# MAX4239_breakout.net
KiCad netlist of a schematic drawn in EAGLE
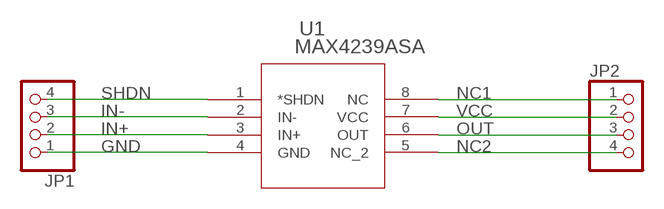
[diagram p0: schematic, sheet 1]

(export (version "E")
  (design (tool "Eeschema 10.0.6"))
  (components
    (comp (ref "JP1")
      (value "PINHD-1X4")
      (footprint "eagle-import:1X04")
      (libsource (lib "eagle-import") (part "PINHD-1X4"))
    )
    (comp (ref "JP2")
      (value "PINHD-1X4")
      (footprint "eagle-import:1X04")
      (libsource (lib "eagle-import") (part "PINHD-1X4"))
    )
    (comp (ref "U1")
      (value "MAX4239ASA")
      (footprint "eagle-import:21-0041B_8")
      (fields (field (name "MF") "Maxim Integrated") (field (name "MP") "MAX4239ASA+"))
      (libsource (lib "eagle-import") (part "MAX4239ASA"))
    )
  )
  (nets
    (net (code "1") (name "/GND") (class "Default")
      (node (ref "JP1") (pin "1") (pinfunction "1_1") (pintype "passive"))
      (node (ref "U1") (pin "4") (pinfunction "GND_4") (pintype "power_in"))
    )
    (net (code "2") (name "/IN+") (class "Default")
      (node (ref "JP1") (pin "2") (pinfunction "2_2") (pintype "passive"))
      (node (ref "U1") (pin "3") (pinfunction "IN+_3") (pintype "input"))
    )
    (net (code "3") (name "/IN-") (class "Default")
      (node (ref "JP1") (pin "3") (pinfunction "3_3") (pintype "passive"))
      (node (ref "U1") (pin "2") (pinfunction "IN-_2") (pintype "input"))
    )
    (net (code "4") (name "/NC1") (class "Default")
      (node (ref "JP2") (pin "1") (pinfunction "1_1") (pintype "passive"))
      (node (ref "U1") (pin "8") (pinfunction "NC_8") (pintype "passive"))
    )
    (net (code "5") (name "/NC2") (class "Default")
      (node (ref "JP2") (pin "4") (pinfunction "4_4") (pintype "passive"))
      (node (ref "U1") (pin "5") (pinfunction "NC_2_5") (pintype "passive"))
    )
    (net (code "6") (name "/OUT") (class "Default")
      (node (ref "JP2") (pin "3") (pinfunction "3_3") (pintype "passive"))
      (node (ref "U1") (pin "6") (pinfunction "OUT_6") (pintype "output"))
    )
    (net (code "7") (name "/SHDN") (class "Default")
      (node (ref "JP1") (pin "4") (pinfunction "4_4") (pintype "passive"))
      (node (ref "U1") (pin "1") (pinfunction "*SHDN_1") (pintype "passive"))
    )
    (net (code "8") (name "/VCC") (class "Default")
      (node (ref "JP2") (pin "2") (pinfunction "2_2") (pintype "passive"))
      (node (ref "U1") (pin "7") (pinfunction "VCC_7") (pintype "power_in"))
    )
  )
)
